# p4_power_measure_ch1.net
KiCad netlist of a schematic drawn in Altium Designer
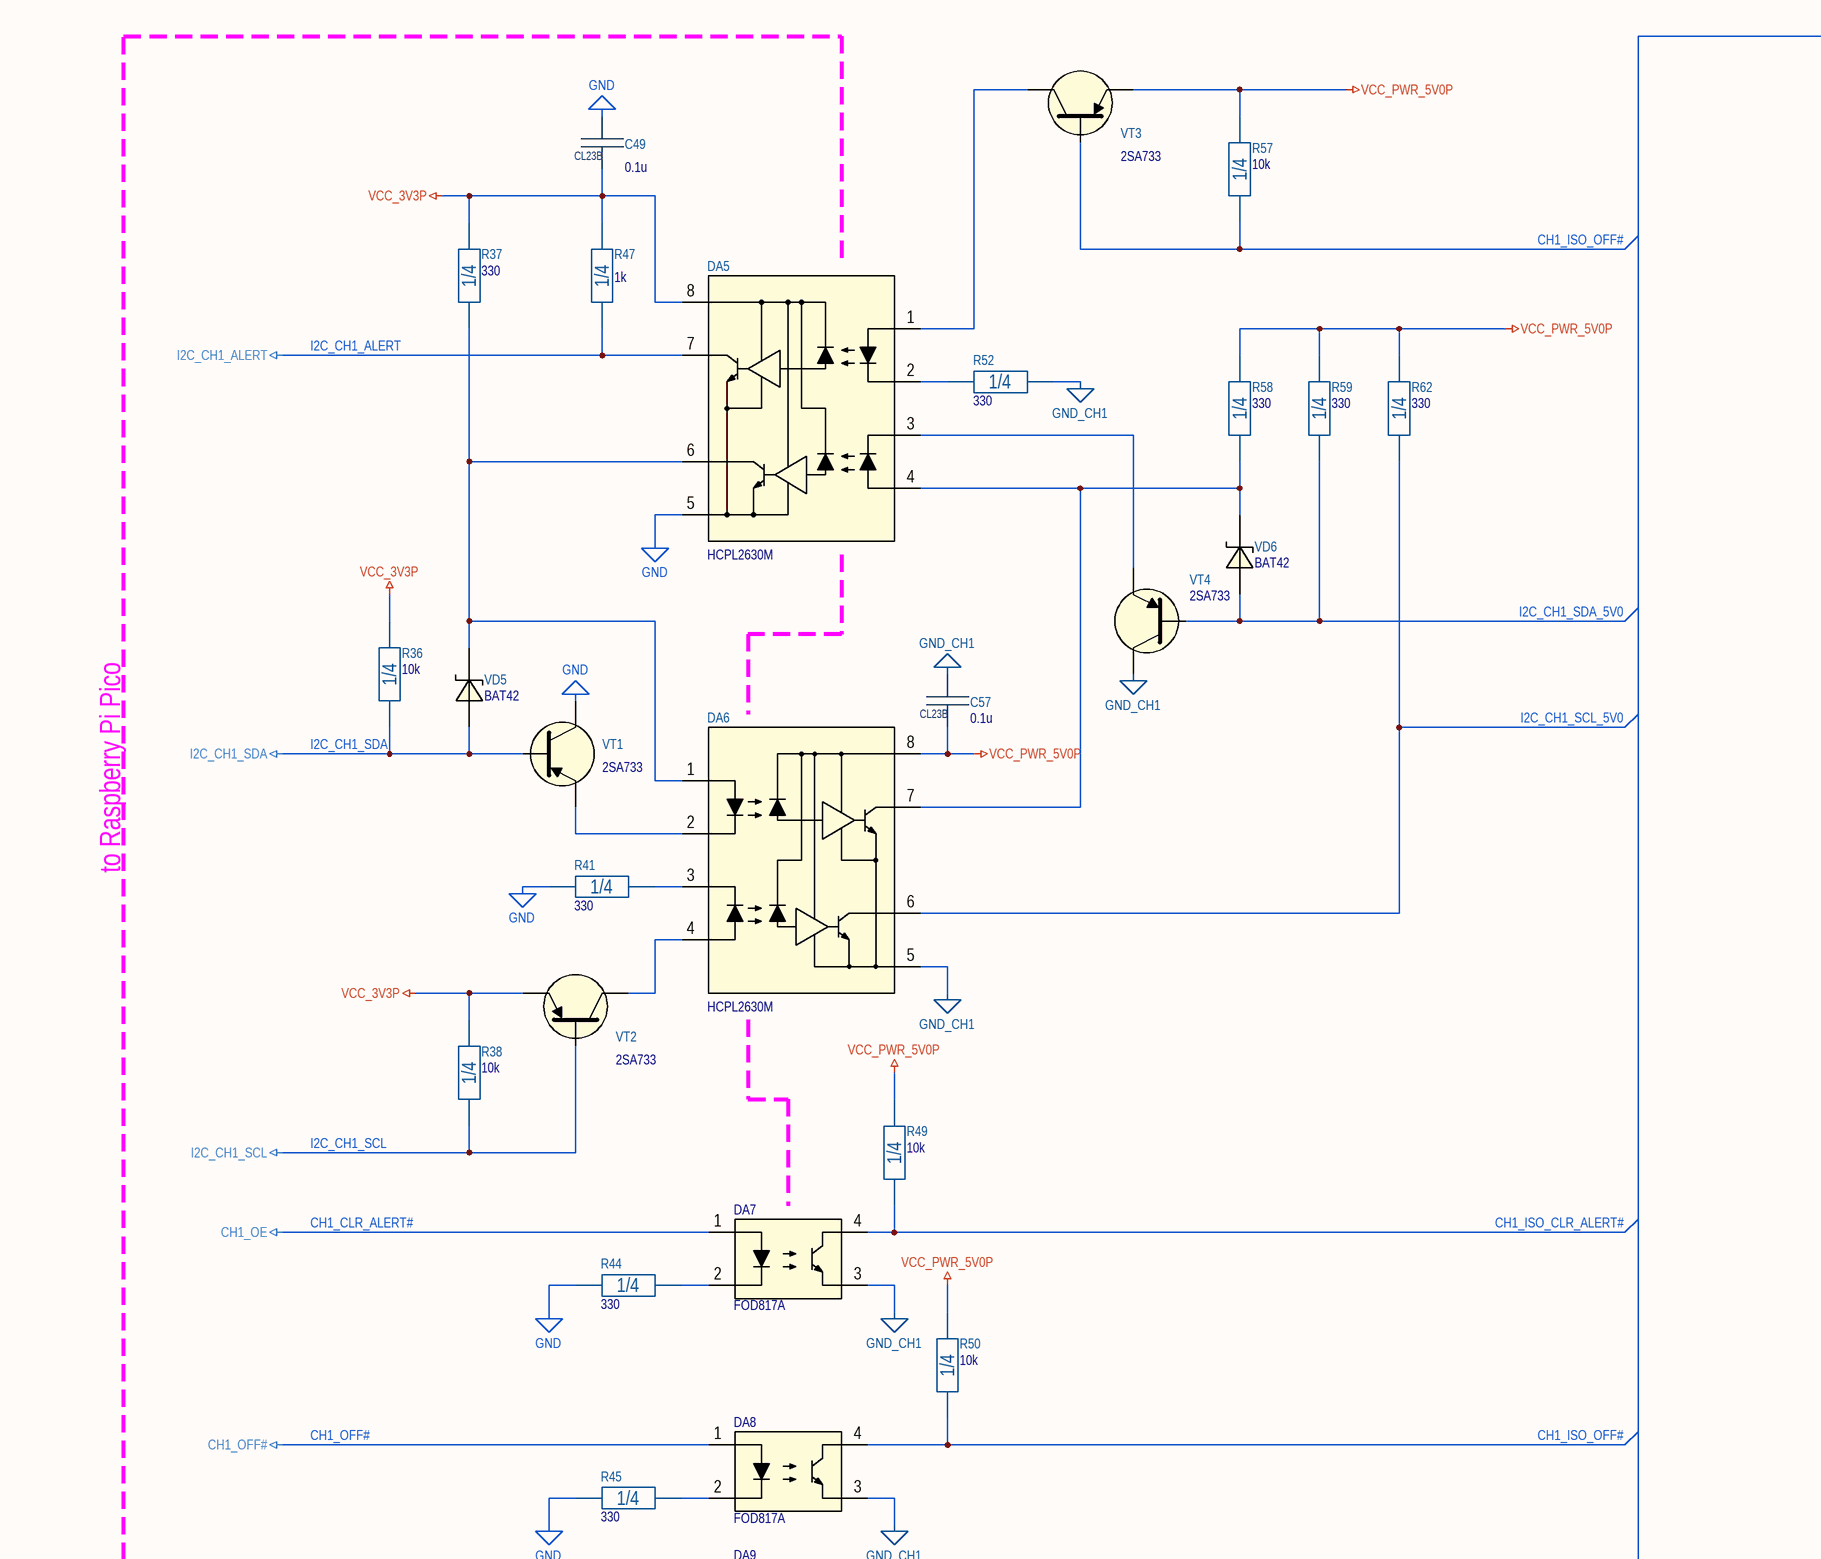
[diagram p0: p4_power_measure_ch1.SchDoc, top left]
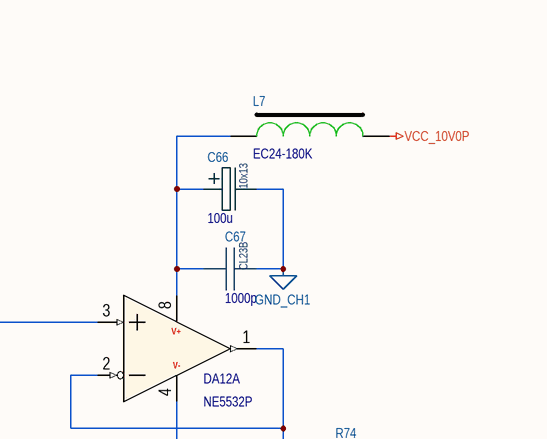
[diagram p1: p4_power_measure_ch1.SchDoc, top right]
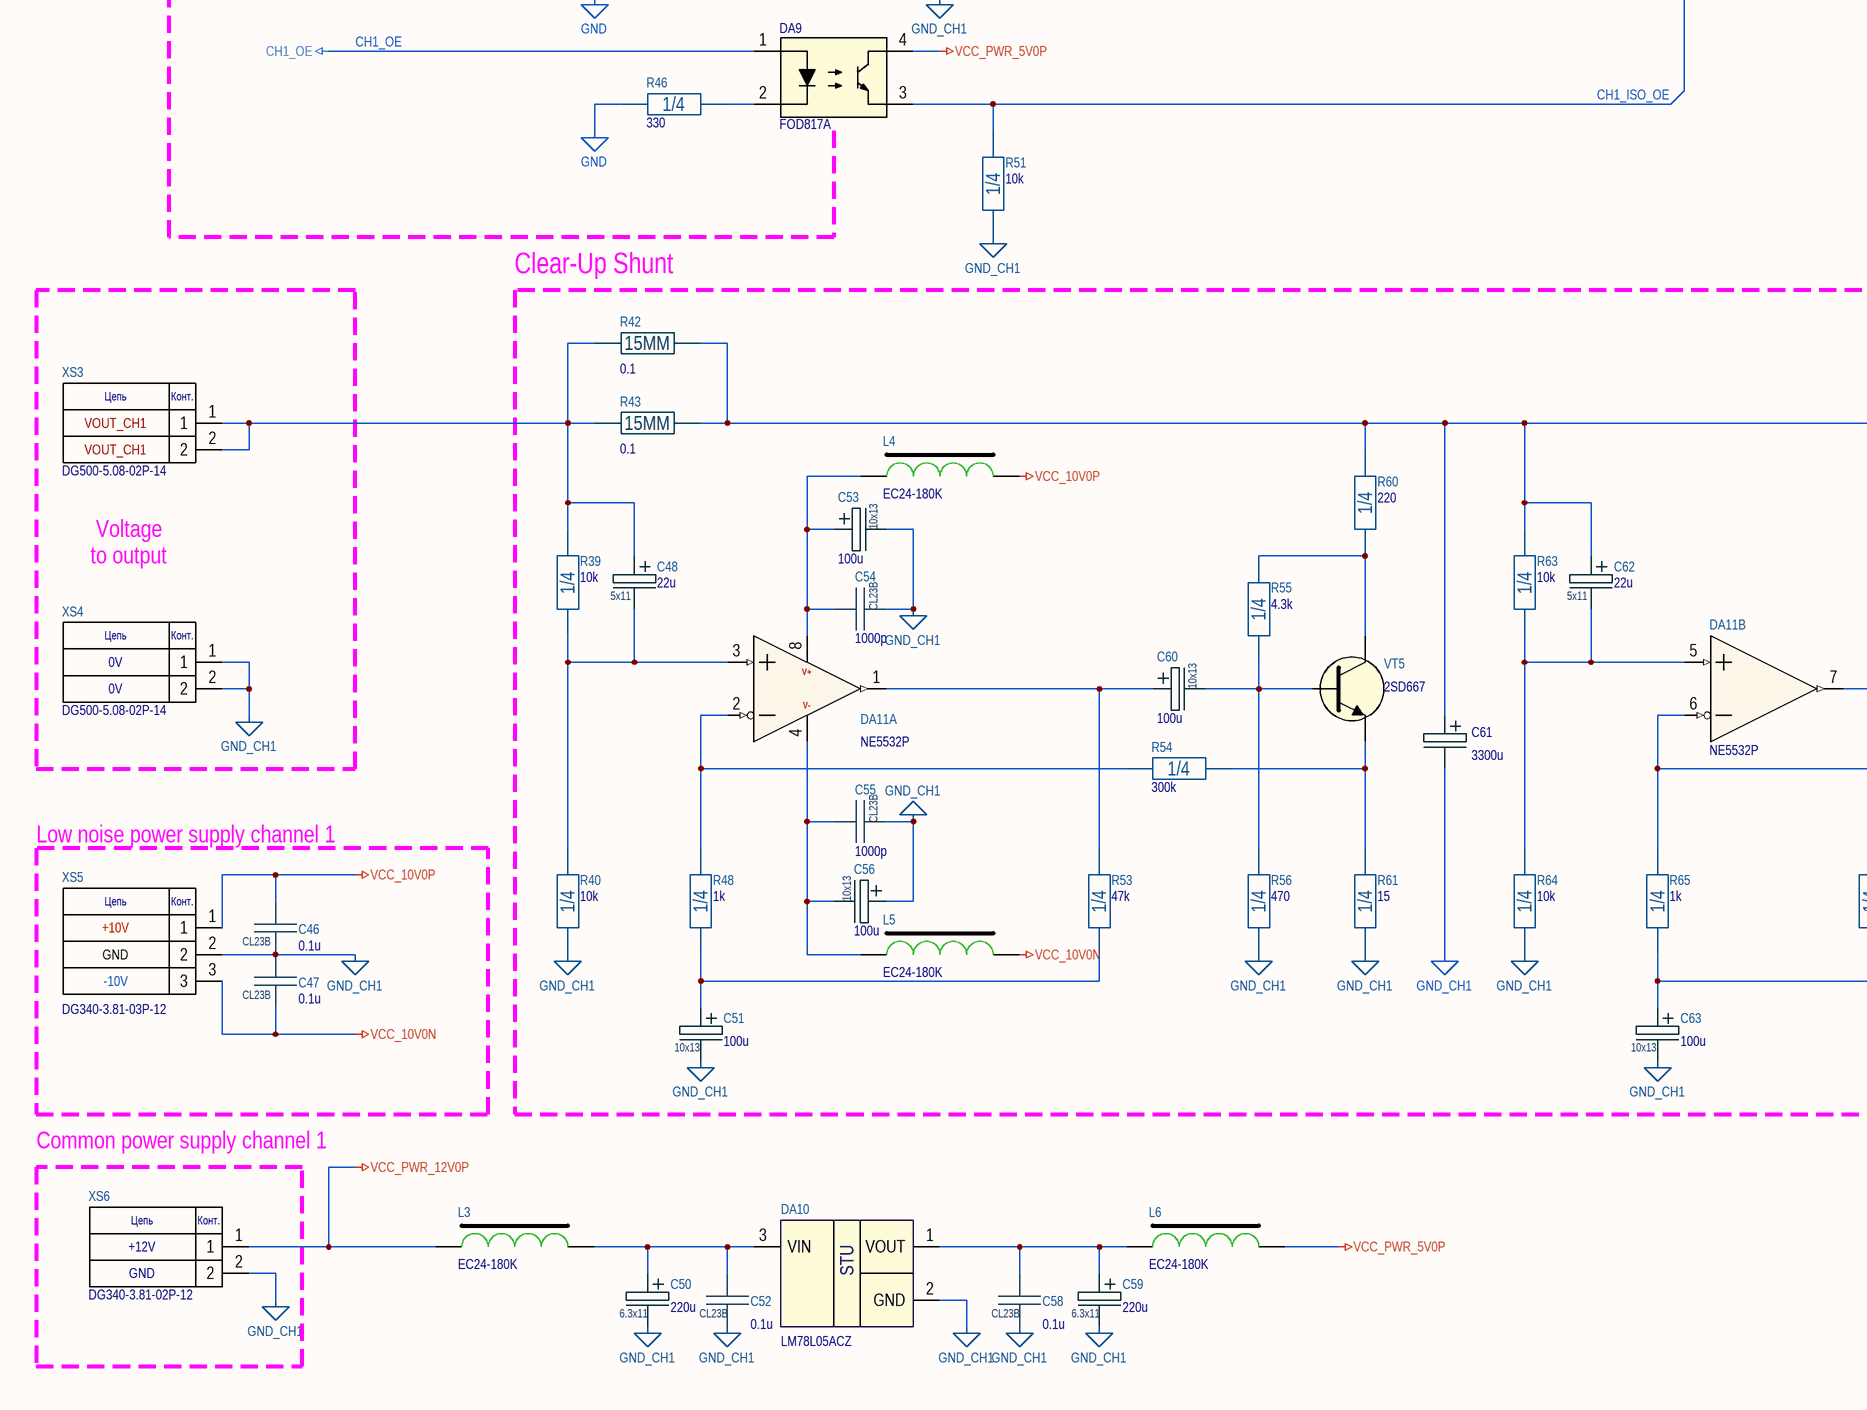
[diagram p2: p4_power_measure_ch1.SchDoc, bottom left]
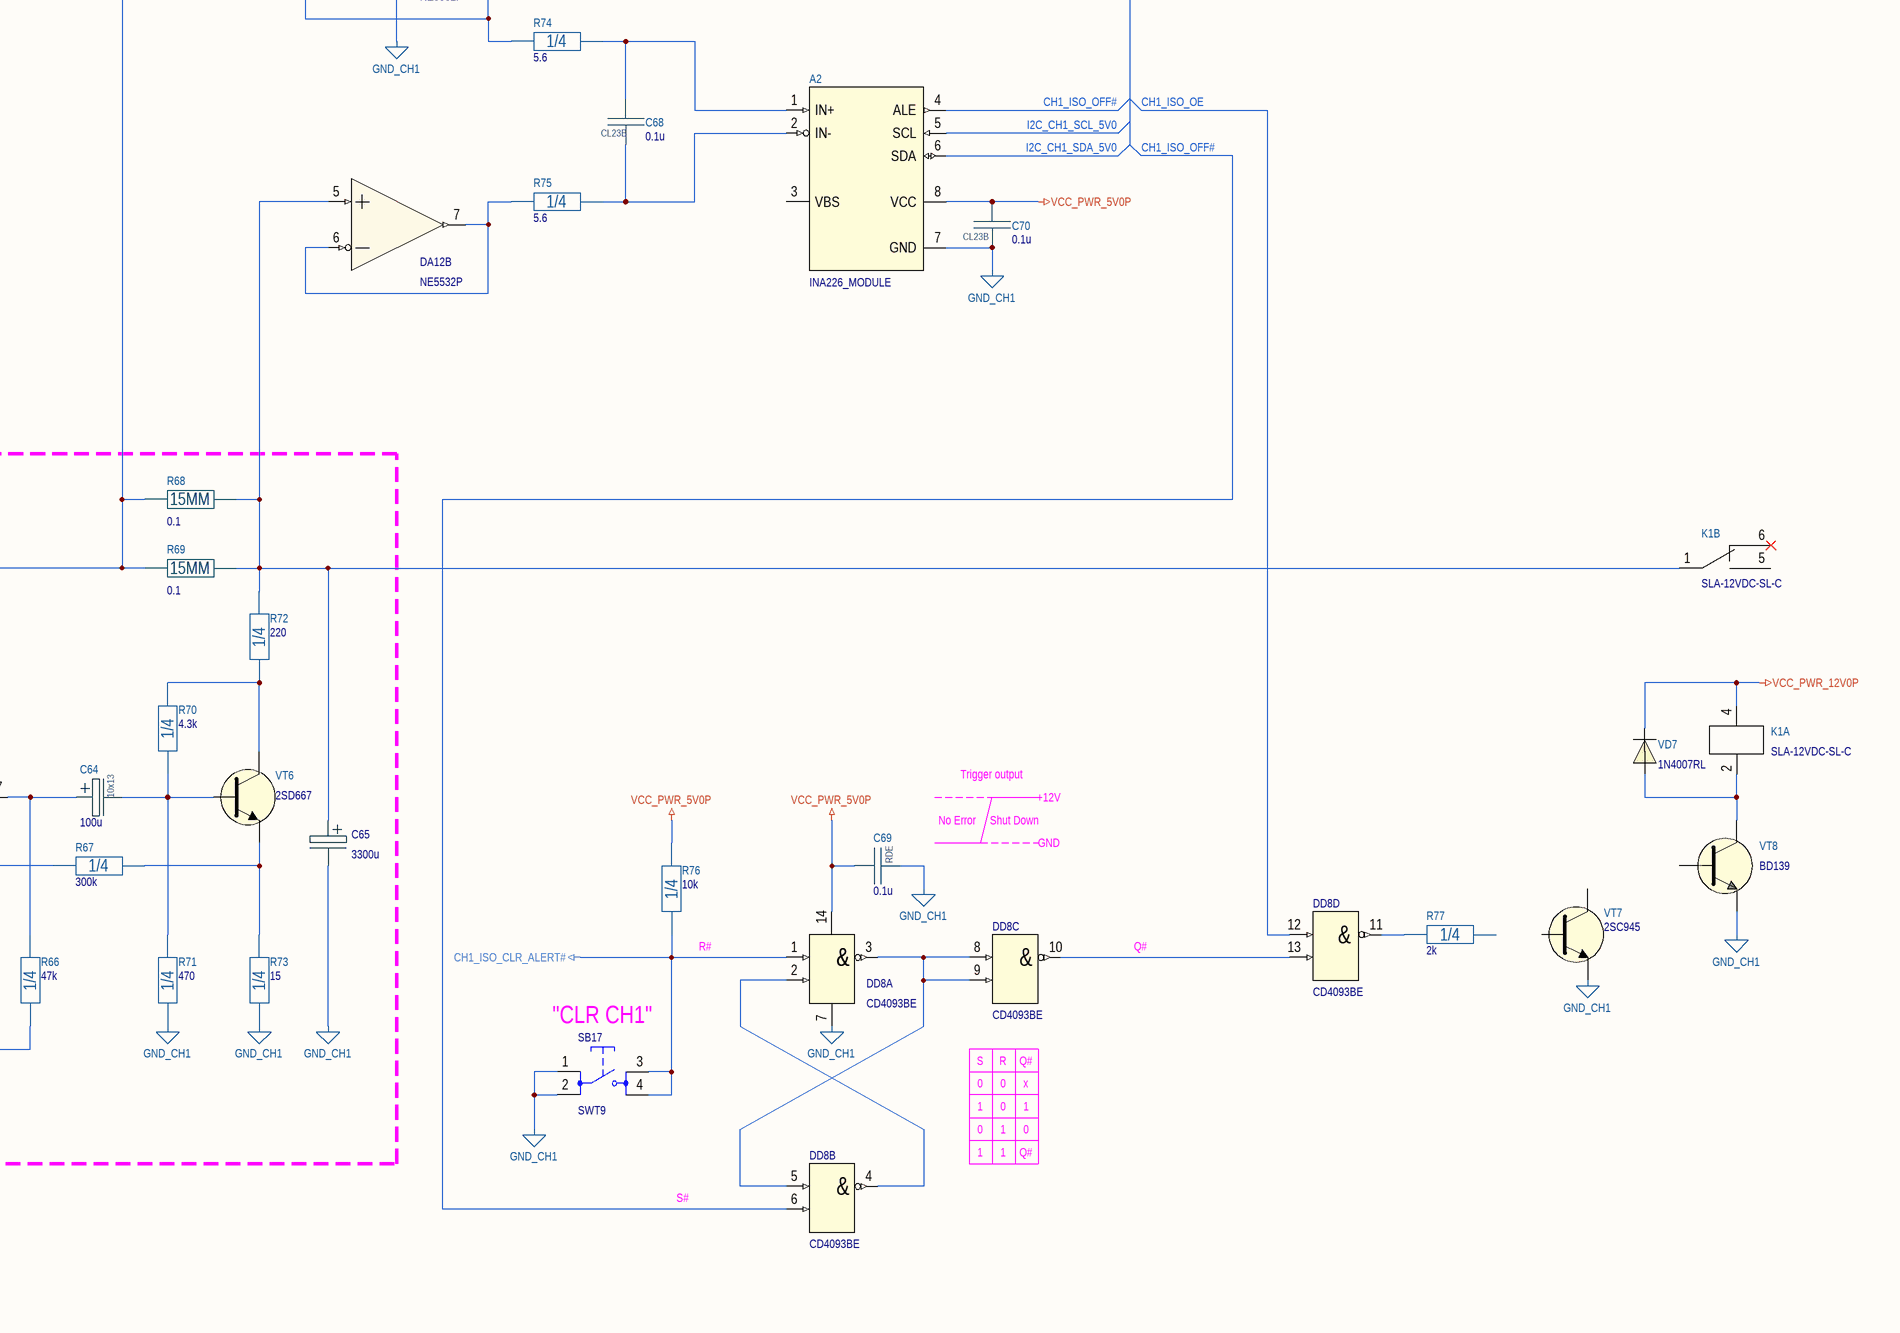
[diagram p3: p4_power_measure_ch1.SchDoc, bottom right]

(export (version "E")
  (design (tool "Eeschema 10.0.6"))
  (components
    (comp (ref "A2")
      (value "INA226_MODULE")
      (footprint "PcbLib_Others:INA226_MODULE_VERT")
      (description "20x20mm module with INA226")
      (libsource (lib "Schlib_OtherComponents") (part "INA226_MODULE"))
    )
    (comp (ref "C46")
      (value "0.1u")
      (footprint "PcbLib_RC:CL23B_7.2x2.5")
      (description "Box-type metallized polyester film capacitor")
      (fields
        (field (name "TOLERANCE") "± * %")
        (field (name "VOLTAGE") "63V")
        (field (name "PACKAGE") "CL23B")
      )
      (libsource (lib "Schlib_RC") (part "CL23B"))
    )
    (comp (ref "C47")
      (value "0.1u")
      (footprint "PcbLib_RC:CL23B_7.2x2.5")
      (description "Box-type metallized polyester film capacitor")
      (fields
        (field (name "TOLERANCE") "± * %")
        (field (name "VOLTAGE") "63V")
        (field (name "PACKAGE") "CL23B")
      )
      (libsource (lib "Schlib_RC") (part "CL23B"))
    )
    (comp (ref "C48")
      (value "22u")
      (footprint "PcbLib_RC:ECAP5X11X2.0_BRW")
      (description "Aluminium capacitor")
      (fields
        (field (name "TOLERANCE") "± 20 %")
        (field (name "VOLTAGE") "63V")
        (field (name "PACKAGE") "5x11")
      )
      (libsource (lib "Schlib_RC") (part "C_ECAP"))
    )
    (comp (ref "C49")
      (value "0.1u")
      (footprint "PcbLib_RC:CL23B_7.2x2.5")
      (description "Box-type metallized polyester film capacitor")
      (fields
        (field (name "TOLERANCE") "± * %")
        (field (name "VOLTAGE") "63V")
        (field (name "PACKAGE") "CL23B")
      )
      (libsource (lib "Schlib_RC") (part "CL23B"))
    )
    (comp (ref "C50")
      (value "220u")
      (footprint "PcbLib_RC:ECAP6.3X11X2.5_BRW")
      (description "Aluminium capacitor")
      (fields
        (field (name "TOLERANCE") "± 20 %")
        (field (name "VOLTAGE") "16V")
        (field (name "PACKAGE") "6.3x11")
      )
      (libsource (lib "Schlib_RC") (part "C_ECAP"))
    )
    (comp (ref "C51")
      (value "100u")
      (footprint "PcbLib_RC:ECAP10X13X5_BRW")
      (description "Aluminium capacitor")
      (fields
        (field (name "TOLERANCE") "± 20 %")
        (field (name "VOLTAGE") "63V")
        (field (name "PACKAGE") "10x13")
      )
      (libsource (lib "Schlib_RC") (part "C_ECAP"))
    )
    (comp (ref "C52")
      (value "0.1u")
      (footprint "PcbLib_RC:CL23B_7.2x2.5")
      (description "Box-type metallized polyester film capacitor")
      (fields
        (field (name "TOLERANCE") "± * %")
        (field (name "VOLTAGE") "63V")
        (field (name "PACKAGE") "CL23B")
      )
      (libsource (lib "Schlib_RC") (part "CL23B"))
    )
    (comp (ref "C53")
      (value "100u")
      (footprint "PcbLib_RC:ECAP10X13X5_BRW")
      (description "Aluminium capacitor")
      (fields
        (field (name "TOLERANCE") "± 20 %")
        (field (name "VOLTAGE") "63V")
        (field (name "PACKAGE") "10x13")
      )
      (libsource (lib "Schlib_RC") (part "C_ECAP"))
    )
    (comp (ref "C54")
      (value "1000p")
      (footprint "PcbLib_RC:CL23B_7.2x2.5")
      (description "Box-type metallized polyester film capacitor")
      (fields
        (field (name "TOLERANCE") "± * %")
        (field (name "VOLTAGE") "63V")
        (field (name "PACKAGE") "CL23B")
      )
      (libsource (lib "Schlib_RC") (part "CL23B"))
    )
    (comp (ref "C55")
      (value "1000p")
      (footprint "PcbLib_RC:CL23B_7.2x2.5")
      (description "Box-type metallized polyester film capacitor")
      (fields
        (field (name "TOLERANCE") "± * %")
        (field (name "VOLTAGE") "63V")
        (field (name "PACKAGE") "CL23B")
      )
      (libsource (lib "Schlib_RC") (part "CL23B"))
    )
    (comp (ref "C56")
      (value "100u")
      (footprint "PcbLib_RC:ECAP10X13X5_BRW")
      (description "Aluminium capacitor")
      (fields
        (field (name "TOLERANCE") "± 20 %")
        (field (name "VOLTAGE") "63V")
        (field (name "PACKAGE") "10x13")
      )
      (libsource (lib "Schlib_RC") (part "C_ECAP"))
    )
    (comp (ref "C57")
      (value "0.1u")
      (footprint "PcbLib_RC:CL23B_7.2x2.5")
      (description "Box-type metallized polyester film capacitor")
      (fields
        (field (name "TOLERANCE") "± * %")
        (field (name "VOLTAGE") "63V")
        (field (name "PACKAGE") "CL23B")
      )
      (libsource (lib "Schlib_RC") (part "CL23B"))
    )
    (comp (ref "C58")
      (value "0.1u")
      (footprint "PcbLib_RC:CL23B_7.2x2.5")
      (description "Box-type metallized polyester film capacitor")
      (fields
        (field (name "TOLERANCE") "± * %")
        (field (name "VOLTAGE") "63V")
        (field (name "PACKAGE") "CL23B")
      )
      (libsource (lib "Schlib_RC") (part "CL23B"))
    )
    (comp (ref "C59")
      (value "220u")
      (footprint "PcbLib_RC:ECAP6.3X11X2.5_BRW")
      (description "Aluminium capacitor")
      (fields
        (field (name "TOLERANCE") "± 20 %")
        (field (name "VOLTAGE") "16V")
        (field (name "PACKAGE") "6.3x11")
      )
      (libsource (lib "Schlib_RC") (part "C_ECAP"))
    )
    (comp (ref "C60")
      (value "100u")
      (footprint "PcbLib_RC:ECAP10X13X5_BRW")
      (description "Aluminium capacitor")
      (fields
        (field (name "TOLERANCE") "± 20 %")
        (field (name "VOLTAGE") "63V")
        (field (name "PACKAGE") "10x13")
      )
      (libsource (lib "Schlib_RC") (part "C_ECAP"))
    )
    (comp (ref "C61")
      (value "3300u")
      (footprint "PcbLib_RC:ECAP16X36X75_BLK")
      (description "Aluminium capacitor")
      (fields (field (name "TOLERANCE") "± 20 %") (field (name "VOLTAGE") "50V"))
      (libsource (lib "Schlib_RC") (part "C_ECAP"))
    )
    (comp (ref "C62")
      (value "22u")
      (footprint "PcbLib_RC:ECAP5X11X2.0_BRW")
      (description "Aluminium capacitor")
      (fields
        (field (name "TOLERANCE") "± 20 %")
        (field (name "VOLTAGE") "63V")
        (field (name "PACKAGE") "5x11")
      )
      (libsource (lib "Schlib_RC") (part "C_ECAP"))
    )
    (comp (ref "C63")
      (value "100u")
      (footprint "PcbLib_RC:ECAP10X13X5_BRW")
      (description "Aluminium capacitor")
      (fields
        (field (name "TOLERANCE") "± 20 %")
        (field (name "VOLTAGE") "63V")
        (field (name "PACKAGE") "10x13")
      )
      (libsource (lib "Schlib_RC") (part "C_ECAP"))
    )
    (comp (ref "C64")
      (value "100u")
      (footprint "PcbLib_RC:ECAP10X13X5_BRW")
      (description "Aluminium capacitor")
      (fields
        (field (name "TOLERANCE") "± 20 %")
        (field (name "VOLTAGE") "63V")
        (field (name "PACKAGE") "10x13")
      )
      (libsource (lib "Schlib_RC") (part "C_ECAP"))
    )
    (comp (ref "C65")
      (value "3300u")
      (footprint "PcbLib_RC:ECAP16X36X75_BLK")
      (description "Aluminium capacitor")
      (fields (field (name "TOLERANCE") "± 20 %") (field (name "VOLTAGE") "50V"))
      (libsource (lib "Schlib_RC") (part "C_ECAP"))
    )
    (comp (ref "C66")
      (value "100u")
      (footprint "PcbLib_RC:ECAP10X13X5_BRW")
      (description "Aluminium capacitor")
      (fields
        (field (name "TOLERANCE") "± 20 %")
        (field (name "VOLTAGE") "63V")
        (field (name "PACKAGE") "10x13")
      )
      (libsource (lib "Schlib_RC") (part "C_ECAP"))
    )
    (comp (ref "C67")
      (value "1000p")
      (footprint "PcbLib_RC:CL23B_7.2x2.5")
      (description "Box-type metallized polyester film capacitor")
      (fields
        (field (name "TOLERANCE") "± * %")
        (field (name "VOLTAGE") "63V")
        (field (name "PACKAGE") "CL23B")
      )
      (libsource (lib "Schlib_RC") (part "CL23B"))
    )
    (comp (ref "C68")
      (value "0.1u")
      (footprint "PcbLib_RC:CL23B_7.2x2.5")
      (description "Box-type metallized polyester film capacitor")
      (fields
        (field (name "TOLERANCE") "± * %")
        (field (name "VOLTAGE") "63V")
        (field (name "PACKAGE") "CL23B")
      )
      (libsource (lib "Schlib_RC") (part "CL23B"))
    )
    (comp (ref "C69")
      (value "0.1u")
      (footprint "PcbLib_RC:RDE_1P1")
      (description "MLCC radial lead type with epoxy coat (RDE Series)")
      (fields
        (field (name "TOLERANCE") "± 10 %")
        (field (name "VOLTAGE") "100V")
        (field (name "PACKAGE") "RDE")
      )
      (libsource (lib "Schlib_RC") (part "RDE_CAP"))
    )
    (comp (ref "C70")
      (value "0.1u")
      (footprint "PcbLib_RC:CL23B_7.2x2.5")
      (description "Box-type metallized polyester film capacitor")
      (fields
        (field (name "TOLERANCE") "± * %")
        (field (name "VOLTAGE") "63V")
        (field (name "PACKAGE") "CL23B")
      )
      (libsource (lib "Schlib_RC") (part "CL23B"))
    )
    (comp (ref "DA5")
      (value "HCPL2630M")
      (footprint "PcbLib_ICs:DIP-8P-M01")
      (description "Dual-Channel High-Speed 10 MBit/s Logic Gate Optocouplers")
      (fields (field (name "MANUFACTURER") "ON Semiconductor"))
      (libsource (lib "Schlib_ONSemiconductor") (part "HCPL2630M"))
    )
    (comp (ref "DA6")
      (value "HCPL2630M")
      (footprint "PcbLib_ICs:DIP-8P-M01")
      (description "Dual-Channel High-Speed 10 MBit/s Logic Gate Optocouplers")
      (fields (field (name "MANUFACTURER") "ON Semiconductor"))
      (libsource (lib "Schlib_ONSemiconductor") (part "HCPL2630M"))
    )
    (comp (ref "DA7")
      (value "FOD817A")
      (footprint "PcbLib_ICs:DIP-4P")
      (description "5kV Phototransistor Optocoupler")
      (fields (field (name "MANUFACTURER") "ON Semiconductor"))
      (libsource (lib "Schlib_ONSemiconductor") (part "FOD817A"))
    )
    (comp (ref "DA8")
      (value "FOD817A")
      (footprint "PcbLib_ICs:DIP-4P")
      (description "5kV Phototransistor Optocoupler")
      (fields (field (name "MANUFACTURER") "ON Semiconductor"))
      (libsource (lib "Schlib_ONSemiconductor") (part "FOD817A"))
    )
    (comp (ref "DA9")
      (value "FOD817A")
      (footprint "PcbLib_ICs:DIP-4P")
      (description "5kV Phototransistor Optocoupler")
      (fields (field (name "MANUFACTURER") "ON Semiconductor"))
      (libsource (lib "Schlib_ONSemiconductor") (part "FOD817A"))
    )
    (comp (ref "DA10")
      (value "LM78L05ACZ")
      (footprint "PcbLib_ICs:TO-92 (VERTICAL,LINE)")
      (description "100-mA Fixed Output Linear Regulator")
      (fields (field (name "MANUFACTURER") "Texas Instruments"))
      (libsource (lib "Schlib_Texas_Instruments") (part "LM78L05ACZ"))
    )
    (comp (ref "DA11")
      (value "NE5532P")
      (footprint "PcbLib_ICs:DIP-8P-M01")
      (description "DUAL LOW-NOISE OPERATIONAL AMPLIFIERS")
      (fields (field (name "MANUFACTURER") "Texas Instruments"))
      (libsource (lib "Schlib_Texas_Instruments") (part "NE5532P"))
    )
    (comp (ref "DA12")
      (value "NE5532P")
      (footprint "PcbLib_ICs:DIP-8P-M01")
      (description "DUAL LOW-NOISE OPERATIONAL AMPLIFIERS")
      (fields (field (name "MANUFACTURER") "Texas Instruments"))
      (libsource (lib "Schlib_Texas_Instruments") (part "NE5532P"))
    )
    (comp (ref "DD8")
      (value "CD4093BE")
      (footprint "PcbLib_ICs:DIP-14P-M02")
      (description "Quad 2-Input NAND Gate Schmitt Triggers")
      (fields (field (name "MANUFACTURER") "Texas Instruments"))
      (libsource (lib "Schlib_Texas_Instruments") (part "CD4093BE"))
    )
    (comp (ref "K1")
      (value "SLA-12VDC-SL-C")
      (footprint "PcbLib_Others:RELAY_32x27.5MM")
      (description "Subminature high power relay 4P 30A")
      (fields (field (name "MANUFACTURER") "Songle Relay"))
      (libsource (lib "") (part "SLA-12VDC-SL-C_1"))
    )
    (comp (ref "L3")
      (value "EC24-180K")
      (footprint "PcbLib_RC:EC24_GREEN")
      (description "Axial leaded coated inductors")
      (fields (field (name "MANUFACTURER") "3L Electronic"))
      (libsource (lib "Schlib_RC") (part "EC24"))
    )
    (comp (ref "L4")
      (value "EC24-180K")
      (footprint "PcbLib_RC:EC24_GREEN")
      (description "Axial leaded coated inductors")
      (fields (field (name "MANUFACTURER") "3L Electronic"))
      (libsource (lib "Schlib_RC") (part "EC24"))
    )
    (comp (ref "L5")
      (value "EC24-180K")
      (footprint "PcbLib_RC:EC24_GREEN")
      (description "Axial leaded coated inductors")
      (fields (field (name "MANUFACTURER") "3L Electronic"))
      (libsource (lib "Schlib_RC") (part "EC24"))
    )
    (comp (ref "L6")
      (value "EC24-180K")
      (footprint "PcbLib_RC:EC24_GREEN")
      (description "Axial leaded coated inductors")
      (fields (field (name "MANUFACTURER") "3L Electronic"))
      (libsource (lib "Schlib_RC") (part "EC24"))
    )
    (comp (ref "L7")
      (value "EC24-180K")
      (footprint "PcbLib_RC:EC24_GREEN")
      (description "Axial leaded coated inductors")
      (fields (field (name "MANUFACTURER") "3L Electronic"))
      (libsource (lib "Schlib_RC") (part "EC24"))
    )
    (comp (ref "R36")
      (value "10k")
      (footprint "PcbLib_RC:CFR-25")
      (description "Resistor 1/4W")
      (fields
        (field (name "TOLERANCE") "± 1 %")
        (field (name "PART NUMBER") "MFR-25FTF52-10K")
        (field (name "PACKAGE") "1/4")
      )
      (libsource (lib "Schlib_RC") (part "CF25"))
    )
    (comp (ref "R37")
      (value "330")
      (footprint "PcbLib_RC:CFR-25")
      (description "Resistor 1/4W")
      (fields
        (field (name "TOLERANCE") "± 1 %")
        (field (name "PART NUMBER") "MFR-25FTF52-330R")
        (field (name "PACKAGE") "1/4")
      )
      (libsource (lib "Schlib_RC") (part "CF25"))
    )
    (comp (ref "R38")
      (value "10k")
      (footprint "PcbLib_RC:CFR-25")
      (description "Resistor 1/4W")
      (fields
        (field (name "TOLERANCE") "± 1 %")
        (field (name "PART NUMBER") "MFR-25FTF52-10K")
        (field (name "PACKAGE") "1/4")
      )
      (libsource (lib "Schlib_RC") (part "CF25"))
    )
    (comp (ref "R39")
      (value "10k")
      (footprint "PcbLib_RC:CFR-25")
      (description "Resistor 1/4W")
      (fields
        (field (name "TOLERANCE") "± 1 %")
        (field (name "PART NUMBER") "MFR-25FTF52-10K")
        (field (name "PACKAGE") "1/4")
      )
      (libsource (lib "Schlib_RC") (part "CF25"))
    )
    (comp (ref "R40")
      (value "10k")
      (footprint "PcbLib_RC:CFR-25")
      (description "Resistor 1/4W")
      (fields
        (field (name "TOLERANCE") "± 1 %")
        (field (name "PART NUMBER") "MFR-25FTF52-10K")
        (field (name "PACKAGE") "1/4")
      )
      (libsource (lib "Schlib_RC") (part "CF25"))
    )
    (comp (ref "R41")
      (value "330")
      (footprint "PcbLib_RC:CFR-25")
      (description "Resistor 1/4W")
      (fields
        (field (name "TOLERANCE") "± 1 %")
        (field (name "PART NUMBER") "MFR-25FTF52-330R")
        (field (name "PACKAGE") "1/4")
      )
      (libsource (lib "Schlib_RC") (part "CF25"))
    )
    (comp (ref "R42")
      (value "0.1")
      (footprint "PcbLib_RC:CURRENT_SENSE_15x18mm")
      (description "Constantan shunt resistor, pitch = 15mm")
      (fields (field (name "TOLERANCE") "±  %") (field (name "PACKAGE") "15MM"))
      (libsource (lib "Schlib_RC") (part "SHUNT_15MM"))
    )
    (comp (ref "R43")
      (value "0.1")
      (footprint "PcbLib_RC:CURRENT_SENSE_15x18mm")
      (description "Constantan shunt resistor, pitch = 15mm")
      (fields (field (name "TOLERANCE") "±  %") (field (name "PACKAGE") "15MM"))
      (libsource (lib "Schlib_RC") (part "SHUNT_15MM"))
    )
    (comp (ref "R44")
      (value "330")
      (footprint "PcbLib_RC:CFR-25")
      (description "Resistor 1/4W")
      (fields
        (field (name "TOLERANCE") "± 1 %")
        (field (name "PART NUMBER") "MFR-25FTF52-330R")
        (field (name "PACKAGE") "1/4")
      )
      (libsource (lib "Schlib_RC") (part "CF25"))
    )
    (comp (ref "R45")
      (value "330")
      (footprint "PcbLib_RC:CFR-25")
      (description "Resistor 1/4W")
      (fields
        (field (name "TOLERANCE") "± 1 %")
        (field (name "PART NUMBER") "MFR-25FTF52-330R")
        (field (name "PACKAGE") "1/4")
      )
      (libsource (lib "Schlib_RC") (part "CF25"))
    )
    (comp (ref "R46")
      (value "330")
      (footprint "PcbLib_RC:CFR-25")
      (description "Resistor 1/4W")
      (fields
        (field (name "TOLERANCE") "± 1 %")
        (field (name "PART NUMBER") "MFR-25FTF52-330R")
        (field (name "PACKAGE") "1/4")
      )
      (libsource (lib "Schlib_RC") (part "CF25"))
    )
    (comp (ref "R47")
      (value "1k")
      (footprint "PcbLib_RC:CFR-25")
      (description "Resistor 1/4W")
      (fields
        (field (name "TOLERANCE") "± 1 %")
        (field (name "PART NUMBER") "MFR-25FTF52-1K")
        (field (name "PACKAGE") "1/4")
      )
      (libsource (lib "Schlib_RC") (part "CF25"))
    )
    (comp (ref "R48")
      (value "1k")
      (footprint "PcbLib_RC:CFR-25")
      (description "Resistor 1/4W")
      (fields
        (field (name "TOLERANCE") "± 1 %")
        (field (name "PART NUMBER") "MFR-25FTF52-1K")
        (field (name "PACKAGE") "1/4")
      )
      (libsource (lib "Schlib_RC") (part "CF25"))
    )
    (comp (ref "R49")
      (value "10k")
      (footprint "PcbLib_RC:CFR-25")
      (description "Resistor 1/4W")
      (fields
        (field (name "TOLERANCE") "± 1 %")
        (field (name "PART NUMBER") "MFR-25FTF52-10K")
        (field (name "PACKAGE") "1/4")
      )
      (libsource (lib "Schlib_RC") (part "CF25"))
    )
    (comp (ref "R50")
      (value "10k")
      (footprint "PcbLib_RC:CFR-25")
      (description "Resistor 1/4W")
      (fields
        (field (name "TOLERANCE") "± 1 %")
        (field (name "PART NUMBER") "MFR-25FTF52-10K")
        (field (name "PACKAGE") "1/4")
      )
      (libsource (lib "Schlib_RC") (part "CF25"))
    )
    (comp (ref "R51")
      (value "10k")
      (footprint "PcbLib_RC:CFR-25")
      (description "Resistor 1/4W")
      (fields
        (field (name "TOLERANCE") "± 1 %")
        (field (name "PART NUMBER") "MFR-25FTF52-10K")
        (field (name "PACKAGE") "1/4")
      )
      (libsource (lib "Schlib_RC") (part "CF25"))
    )
    (comp (ref "R52")
      (value "330")
      (footprint "PcbLib_RC:CFR-25")
      (description "Resistor 1/4W")
      (fields
        (field (name "TOLERANCE") "± 1 %")
        (field (name "PART NUMBER") "MFR-25FTF52-330R")
        (field (name "PACKAGE") "1/4")
      )
      (libsource (lib "Schlib_RC") (part "CF25"))
    )
    (comp (ref "R53")
      (value "47k")
      (footprint "PcbLib_RC:CFR-25")
      (description "Resistor 1/4W")
      (fields
        (field (name "TOLERANCE") "± 1 %")
        (field (name "PART NUMBER") "MFR-25FTF52-47K")
        (field (name "PACKAGE") "1/4")
      )
      (libsource (lib "Schlib_RC") (part "CF25"))
    )
    (comp (ref "R54")
      (value "300k")
      (footprint "PcbLib_RC:CFR-25")
      (description "Resistor 1/4W")
      (fields
        (field (name "TOLERANCE") "± 1 %")
        (field (name "PART NUMBER") "MFR-25FTF52-300K")
        (field (name "PACKAGE") "1/4")
      )
      (libsource (lib "Schlib_RC") (part "CF25"))
    )
    (comp (ref "R55")
      (value "4.3k")
      (footprint "PcbLib_RC:CFR-25")
      (description "Resistor 1/4W")
      (fields
        (field (name "TOLERANCE") "± 1 %")
        (field (name "PART NUMBER") "MFR-25FTF52-4K3")
        (field (name "PACKAGE") "1/4")
      )
      (libsource (lib "Schlib_RC") (part "CF25"))
    )
    (comp (ref "R56")
      (value "470")
      (footprint "PcbLib_RC:CFR-25")
      (description "Resistor 1/4W")
      (fields
        (field (name "TOLERANCE") "± 1 %")
        (field (name "PART NUMBER") "MFR-25FTF52-470R")
        (field (name "PACKAGE") "1/4")
      )
      (libsource (lib "Schlib_RC") (part "CF25"))
    )
    (comp (ref "R57")
      (value "10k")
      (footprint "PcbLib_RC:CFR-25")
      (description "Resistor 1/4W")
      (fields
        (field (name "TOLERANCE") "± 1 %")
        (field (name "PART NUMBER") "MFR-25FTF52-10K")
        (field (name "PACKAGE") "1/4")
      )
      (libsource (lib "Schlib_RC") (part "CF25"))
    )
    (comp (ref "R58")
      (value "330")
      (footprint "PcbLib_RC:CFR-25")
      (description "Resistor 1/4W")
      (fields
        (field (name "TOLERANCE") "± 1 %")
        (field (name "PART NUMBER") "MFR-25FTF52-330R")
        (field (name "PACKAGE") "1/4")
      )
      (libsource (lib "Schlib_RC") (part "CF25"))
    )
    (comp (ref "R59")
      (value "330")
      (footprint "PcbLib_RC:CFR-25")
      (description "Resistor 1/4W")
      (fields
        (field (name "TOLERANCE") "± 1 %")
        (field (name "PART NUMBER") "MFR-25FTF52-330R")
        (field (name "PACKAGE") "1/4")
      )
      (libsource (lib "Schlib_RC") (part "CF25"))
    )
    (comp (ref "R60")
      (value "220")
      (footprint "PcbLib_RC:CFR-25")
      (description "Resistor 1/4W")
      (fields
        (field (name "TOLERANCE") "± 1 %")
        (field (name "PART NUMBER") "MFR-25FTF52-220R")
        (field (name "PACKAGE") "1/4")
      )
      (libsource (lib "Schlib_RC") (part "CF25"))
    )
    (comp (ref "R61")
      (value "15")
      (footprint "PcbLib_RC:CFR-25")
      (description "Resistor 1/4W")
      (fields
        (field (name "TOLERANCE") "± 1 %")
        (field (name "PART NUMBER") "MFR-25FTF52-15R")
        (field (name "PACKAGE") "1/4")
      )
      (libsource (lib "Schlib_RC") (part "CF25"))
    )
    (comp (ref "R62")
      (value "330")
      (footprint "PcbLib_RC:CFR-25")
      (description "Resistor 1/4W")
      (fields
        (field (name "TOLERANCE") "± 1 %")
        (field (name "PART NUMBER") "MFR-25FTF52-330R")
        (field (name "PACKAGE") "1/4")
      )
      (libsource (lib "Schlib_RC") (part "CF25"))
    )
    (comp (ref "R63")
      (value "10k")
      (footprint "PcbLib_RC:CFR-25")
      (description "Resistor 1/4W")
      (fields
        (field (name "TOLERANCE") "± 1 %")
        (field (name "PART NUMBER") "MFR-25FTF52-10K")
        (field (name "PACKAGE") "1/4")
      )
      (libsource (lib "Schlib_RC") (part "CF25"))
    )
    (comp (ref "R64")
      (value "10k")
      (footprint "PcbLib_RC:CFR-25")
      (description "Resistor 1/4W")
      (fields
        (field (name "TOLERANCE") "± 1 %")
        (field (name "PART NUMBER") "MFR-25FTF52-10K")
        (field (name "PACKAGE") "1/4")
      )
      (libsource (lib "Schlib_RC") (part "CF25"))
    )
    (comp (ref "R65")
      (value "1k")
      (footprint "PcbLib_RC:CFR-25")
      (description "Resistor 1/4W")
      (fields
        (field (name "TOLERANCE") "± 1 %")
        (field (name "PART NUMBER") "MFR-25FTF52-1K")
        (field (name "PACKAGE") "1/4")
      )
      (libsource (lib "Schlib_RC") (part "CF25"))
    )
    (comp (ref "R66")
      (value "47k")
      (footprint "PcbLib_RC:CFR-25")
      (description "Resistor 1/4W")
      (fields
        (field (name "TOLERANCE") "± 1 %")
        (field (name "PART NUMBER") "MFR-25FTF52-47K")
        (field (name "PACKAGE") "1/4")
      )
      (libsource (lib "Schlib_RC") (part "CF25"))
    )
    (comp (ref "R67")
      (value "300k")
      (footprint "PcbLib_RC:CFR-25")
      (description "Resistor 1/4W")
      (fields
        (field (name "TOLERANCE") "± 1 %")
        (field (name "PART NUMBER") "MFR-25FTF52-300K")
        (field (name "PACKAGE") "1/4")
      )
      (libsource (lib "Schlib_RC") (part "CF25"))
    )
    (comp (ref "R68")
      (value "0.1")
      (footprint "PcbLib_RC:CURRENT_SENSE_15x18mm")
      (description "Constantan shunt resistor, pitch = 15mm")
      (fields (field (name "TOLERANCE") "±  %") (field (name "PACKAGE") "15MM"))
      (libsource (lib "Schlib_RC") (part "SHUNT_15MM"))
    )
    (comp (ref "R69")
      (value "0.1")
      (footprint "PcbLib_RC:CURRENT_SENSE_15x18mm")
      (description "Constantan shunt resistor, pitch = 15mm")
      (fields (field (name "TOLERANCE") "±  %") (field (name "PACKAGE") "15MM"))
      (libsource (lib "Schlib_RC") (part "SHUNT_15MM"))
    )
    (comp (ref "R70")
      (value "4.3k")
      (footprint "PcbLib_RC:CFR-25")
      (description "Resistor 1/4W")
      (fields
        (field (name "TOLERANCE") "± 1 %")
        (field (name "PART NUMBER") "MFR-25FTF52-4K3")
        (field (name "PACKAGE") "1/4")
      )
      (libsource (lib "Schlib_RC") (part "CF25"))
    )
    (comp (ref "R71")
      (value "470")
      (footprint "PcbLib_RC:CFR-25")
      (description "Resistor 1/4W")
      (fields
        (field (name "TOLERANCE") "± 1 %")
        (field (name "PART NUMBER") "MFR-25FTF52-470R")
        (field (name "PACKAGE") "1/4")
      )
      (libsource (lib "Schlib_RC") (part "CF25"))
    )
    (comp (ref "R72")
      (value "220")
      (footprint "PcbLib_RC:CFR-25")
      (description "Resistor 1/4W")
      (fields
        (field (name "TOLERANCE") "± 1 %")
        (field (name "PART NUMBER") "MFR-25FTF52-220R")
        (field (name "PACKAGE") "1/4")
      )
      (libsource (lib "Schlib_RC") (part "CF25"))
    )
    (comp (ref "R73")
      (value "15")
      (footprint "PcbLib_RC:CFR-25")
      (description "Resistor 1/4W")
      (fields
        (field (name "TOLERANCE") "± 1 %")
        (field (name "PART NUMBER") "MFR-25FTF52-15R")
        (field (name "PACKAGE") "1/4")
      )
      (libsource (lib "Schlib_RC") (part "CF25"))
    )
    (comp (ref "R74")
      (value "5.6")
      (footprint "PcbLib_RC:CFR-25(VERTICAL)")
      (description "Resistor 1/4W")
      (fields
        (field (name "TOLERANCE") "± 1 %")
        (field (name "PART NUMBER") "MFR-25FTF52-5R6")
        (field (name "PACKAGE") "1/4")
      )
      (libsource (lib "Schlib_RC") (part "CF25"))
    )
    (comp (ref "R75")
      (value "5.6")
      (footprint "PcbLib_RC:CFR-25(VERTICAL)")
      (description "Resistor 1/4W")
      (fields
        (field (name "TOLERANCE") "± 1 %")
        (field (name "PART NUMBER") "MFR-25FTF52-5R6")
        (field (name "PACKAGE") "1/4")
      )
      (libsource (lib "Schlib_RC") (part "CF25"))
    )
    (comp (ref "R76")
      (value "10k")
      (footprint "PcbLib_RC:CFR-25")
      (description "Resistor 1/4W")
      (fields
        (field (name "TOLERANCE") "± 1 %")
        (field (name "PART NUMBER") "MFR-25FTF52-10K")
        (field (name "PACKAGE") "1/4")
      )
      (libsource (lib "Schlib_RC") (part "CF25"))
    )
    (comp (ref "R77")
      (value "2k")
      (footprint "PcbLib_RC:CFR-25")
      (description "Resistor 1/4W")
      (fields
        (field (name "TOLERANCE") "± 1 %")
        (field (name "PART NUMBER") "MFR-25FTF52-2K")
        (field (name "PACKAGE") "1/4")
      )
      (libsource (lib "Schlib_RC") (part "CF25"))
    )
    (comp (ref "SB17")
      (value "SWT9")
      (footprint "PcbLib_Others:SWT9")
      (description "Tact Button (with tact cap SWT9S)")
      (libsource (lib "Schlib_OtherComponents") (part "SWT9"))
    )
    (comp (ref "VD5")
      (value "BAT42")
      (footprint "PcbLib_Discrete:DO-35 GLASS BLUE")
      (description "Small signal schottky diode 30V @ 200mA")
      (fields (field (name "MANUFACTURER") "STMicroelectronics"))
      (libsource (lib "Schlib_STMicroelectronics") (part "BAT42"))
    )
    (comp (ref "VD6")
      (value "BAT42")
      (footprint "PcbLib_Discrete:DO-35 GLASS BLUE")
      (description "Small signal schottky diode 30V @ 200mA")
      (fields (field (name "MANUFACTURER") "STMicroelectronics"))
      (libsource (lib "Schlib_STMicroelectronics") (part "BAT42"))
    )
    (comp (ref "VD7")
      (value "1N4007RL")
      (footprint "PcbLib_Discrete:DO-41")
      (description "1A 1000V Standard Recovery Rectifiers Diode")
      (fields (field (name "MANUFACTURER") "ON Semiconductor"))
      (libsource (lib "Schlib_ONSemiconductor") (part "1N4007RL"))
    )
    (comp (ref "VT1")
      (value "2SA733")
      (footprint "PcbLib_ICs:TO-92 (VERTICAL,LINE)")
      (description "General Purpose p-n-p Transistors")
      (fields (field (name "MANUFACTURER") "NEC"))
      (libsource (lib "Schlib_NEC") (part "2SA733"))
    )
    (comp (ref "VT2")
      (value "2SA733")
      (footprint "PcbLib_ICs:TO-92 (VERTICAL,LINE)")
      (description "General Purpose p-n-p Transistors")
      (fields (field (name "MANUFACTURER") "NEC"))
      (libsource (lib "Schlib_NEC") (part "2SA733"))
    )
    (comp (ref "VT3")
      (value "2SA733")
      (footprint "PcbLib_ICs:TO-92 (VERTICAL,LINE)")
      (description "General Purpose p-n-p Transistors")
      (fields (field (name "MANUFACTURER") "NEC"))
      (libsource (lib "Schlib_NEC") (part "2SA733"))
    )
    (comp (ref "VT4")
      (value "2SA733")
      (footprint "PcbLib_ICs:TO-92 (VERTICAL,LINE)")
      (description "General Purpose p-n-p Transistors")
      (fields (field (name "MANUFACTURER") "NEC"))
      (libsource (lib "Schlib_NEC") (part "2SA733"))
    )
    (comp (ref "VT5")
      (value "2SD667")
      (footprint "PcbLib_ICs:TO-92L (VERTICAL,LINE)")
      (description "General Purpose n-p-n Transistors 120V, 1A")
      (fields (field (name "MANUFACTURER") "Secos"))
      (libsource (lib "Schlib_OtherComponents") (part "2SD667"))
    )
    (comp (ref "VT6")
      (value "2SD667")
      (footprint "PcbLib_ICs:TO-92L (VERTICAL,LINE)")
      (description "General Purpose n-p-n Transistors 120V, 1A")
      (fields (field (name "MANUFACTURER") "Secos"))
      (libsource (lib "Schlib_OtherComponents") (part "2SD667"))
    )
    (comp (ref "VT7")
      (value "2SC945")
      (footprint "PcbLib_ICs:TO-92 (VERTICAL,LINE)")
      (description "General Purpose n-p-n Transistors")
      (fields (field (name "MANUFACTURER") "NEC"))
      (libsource (lib "Schlib_NEC") (part "2SC945"))
    )
    (comp (ref "VT8")
      (value "BD139")
      (footprint "PcbLib_ICs:TO-126 (VERTICAL)")
      (description "General Purpose n-p-n Transistors")
      (fields (field (name "MANUFACTURER") "STMicroelectronics"))
      (libsource (lib "Schlib_STMicroelectronics") (part "BD139"))
    )
    (comp (ref "XS3")
      (value "DG500-5.08-02P-14")
      (footprint "PcbLib_Connectors:DG500-5.08-02P")
      (description "2-way screw terminal, pitch 200mils (5.08mm)")
      (fields (field (name "MANUFACTURER") "DEGSON"))
      (libsource (lib "Schlib_OtherComponents") (part "DG500-5.08-02P-14"))
    )
    (comp (ref "XS4")
      (value "DG500-5.08-02P-14")
      (footprint "PcbLib_Connectors:DG500-5.08-02P")
      (description "2-way screw terminal, pitch 200mils (5.08mm)")
      (fields (field (name "MANUFACTURER") "DEGSON"))
      (libsource (lib "Schlib_OtherComponents") (part "DG500-5.08-02P-14"))
    )
    (comp (ref "XS5")
      (value "DG340-3.81-03P-12")
      (footprint "PcbLib_Connectors:DG340-3.81-03P")
      (description "3-way screw terminal, pitch 150mils (3.81mm)")
      (fields (field (name "MANUFACTURER") "DEGSON"))
      (libsource (lib "Schlib_OtherComponents") (part "DG340-3.81-03P-12"))
    )
    (comp (ref "XS6")
      (value "DG340-3.81-02P-12")
      (footprint "PcbLib_Connectors:DG340-3.81-02P")
      (description "2-way screw terminal, pitch 150mils (3.81mm)")
      (fields (field (name "MANUFACTURER") "DEGSON"))
      (libsource (lib "Schlib_OtherComponents") (part "DG340-3.81-02P-12"))
    )
  )
  (nets
    (net (code "1") (name "/CH1_ISO_OE") (class "Default")
      (node (ref "DA9") (pin "3") (pinfunction "EMITTER_3") (pintype "passive"))
      (node (ref "DD8") (pin "12") (pinfunction "A3_12") (pintype "input"))
      (node (ref "R51") (pin "2") (pinfunction "2_2") (pintype "passive"))
    )
    (net (code "2") (name "/CH1_ISO_OFF#") (class "Default")
      (node (ref "A2") (pin "4") (pinfunction "ALE_4") (pintype "output"))
      (node (ref "DA8") (pin "4") (pinfunction "COLLECTOR_4") (pintype "passive"))
      (node (ref "DD8") (pin "6") (pinfunction "B1_6") (pintype "input"))
      (node (ref "R50") (pin "1") (pinfunction "1_1") (pintype "passive"))
      (node (ref "R57") (pin "1") (pinfunction "1_1") (pintype "passive"))
      (node (ref "VT3") (pin "1") (pinfunction "B_1") (pintype "passive"))
    )
    (net (code "3") (name "/I2C_CH1_SCL_5V0") (class "Default")
      (node (ref "A2") (pin "5") (pinfunction "SCL_5") (pintype "input"))
      (node (ref "DA6") (pin "6") (pinfunction "V02_6") (pintype "passive"))
      (node (ref "R62") (pin "2") (pinfunction "2_2") (pintype "passive"))
    )
    (net (code "4") (name "/I2C_CH1_SDA_5V0") (class "Default")
      (node (ref "A2") (pin "6") (pinfunction "SDA_6") (pintype "bidirectional"))
      (node (ref "R59") (pin "2") (pinfunction "2_2") (pintype "passive"))
      (node (ref "VD6") (pin "2") (pinfunction "ANODE_2") (pintype "passive"))
      (node (ref "VT4") (pin "1") (pinfunction "B_1") (pintype "passive"))
    )
    (net (code "5") (name "CH1_ISO_CLR_ALERT#") (class "Default")
      (node (ref "DA7") (pin "4") (pinfunction "COLLECTOR_4") (pintype "passive"))
      (node (ref "DD8") (pin "1") (pinfunction "A0_1") (pintype "input"))
      (node (ref "R49") (pin "1") (pinfunction "1_1") (pintype "passive"))
      (node (ref "R76") (pin "1") (pinfunction "1_1") (pintype "passive"))
      (node (ref "SB17") (pin "3") (pinfunction "3_3") (pintype "passive"))
      (node (ref "SB17") (pin "4") (pinfunction "4_4") (pintype "passive"))
    )
    (net (code "6") (name "CH1_OE") (class "Default")
      (node (ref "DA7") (pin "1") (pinfunction "ANODE_1") (pintype "passive"))
      (node (ref "DA9") (pin "1") (pinfunction "ANODE_1") (pintype "passive"))
    )
    (net (code "7") (name "CH1_OFF#") (class "Default")
      (node (ref "DA8") (pin "1") (pinfunction "ANODE_1") (pintype "passive"))
    )
    (net (code "8") (name "GND") (class "Default")
      (node (ref "C49") (pin "1") (pinfunction "1_1") (pintype "passive"))
      (node (ref "DA5") (pin "5") (pinfunction "GND_5") (pintype "passive"))
      (node (ref "R41") (pin "1") (pinfunction "1_1") (pintype "passive"))
      (node (ref "R44") (pin "1") (pinfunction "1_1") (pintype "passive"))
      (node (ref "R45") (pin "1") (pinfunction "1_1") (pintype "passive"))
      (node (ref "R46") (pin "1") (pinfunction "1_1") (pintype "passive"))
      (node (ref "VT1") (pin "2") (pinfunction "C_2") (pintype "passive"))
    )
    (net (code "9") (name "GND_CH1") (class "Default")
      (node (ref "A2") (pin "7") (pinfunction "GND_7") (pintype "power_in"))
      (node (ref "C46") (pin "2") (pinfunction "2_2") (pintype "passive"))
      (node (ref "C47") (pin "1") (pinfunction "1_1") (pintype "passive"))
      (node (ref "C50") (pin "2") (pinfunction "2_2") (pintype "passive"))
      (node (ref "C51") (pin "2") (pinfunction "2_2") (pintype "passive"))
      (node (ref "C52") (pin "2") (pinfunction "2_2") (pintype "passive"))
      (node (ref "C53") (pin "2") (pinfunction "2_2") (pintype "passive"))
      (node (ref "C54") (pin "2") (pinfunction "2_2") (pintype "passive"))
      (node (ref "C55") (pin "2") (pinfunction "2_2") (pintype "passive"))
      (node (ref "C56") (pin "1") (pinfunction "1_1") (pintype "passive"))
      (node (ref "C57") (pin "1") (pinfunction "1_1") (pintype "passive"))
      (node (ref "C58") (pin "2") (pinfunction "2_2") (pintype "passive"))
      (node (ref "C59") (pin "2") (pinfunction "2_2") (pintype "passive"))
      (node (ref "C61") (pin "2") (pinfunction "2_2") (pintype "passive"))
      (node (ref "C63") (pin "2") (pinfunction "2_2") (pintype "passive"))
      (node (ref "C65") (pin "2") (pinfunction "2_2") (pintype "passive"))
      (node (ref "C66") (pin "2") (pinfunction "2_2") (pintype "passive"))
      (node (ref "C67") (pin "2") (pinfunction "2_2") (pintype "passive"))
      (node (ref "C69") (pin "2") (pinfunction "2_2") (pintype "passive"))
      (node (ref "C70") (pin "2") (pinfunction "2_2") (pintype "passive"))
      (node (ref "DA10") (pin "2") (pinfunction "GND_2") (pintype "power_in"))
      (node (ref "DA12") (pin "4") (pinfunction "GND_4") (pintype "power_in"))
      (node (ref "DA6") (pin "5") (pinfunction "GND_5") (pintype "passive"))
      (node (ref "DA7") (pin "3") (pinfunction "EMITTER_3") (pintype "passive"))
      (node (ref "DA8") (pin "3") (pinfunction "EMITTER_3") (pintype "passive"))
      (node (ref "DD8") (pin "7") (pinfunction "GND_7") (pintype "power_in"))
      (node (ref "R40") (pin "1") (pinfunction "1_1") (pintype "passive"))
      (node (ref "R51") (pin "1") (pinfunction "1_1") (pintype "passive"))
      (node (ref "R52") (pin "2") (pinfunction "2_2") (pintype "passive"))
      (node (ref "R56") (pin "1") (pinfunction "1_1") (pintype "passive"))
      (node (ref "R61") (pin "1") (pinfunction "1_1") (pintype "passive"))
      (node (ref "R64") (pin "1") (pinfunction "1_1") (pintype "passive"))
      (node (ref "R71") (pin "1") (pinfunction "1_1") (pintype "passive"))
      (node (ref "R73") (pin "1") (pinfunction "1_1") (pintype "passive"))
      (node (ref "SB17") (pin "1") (pinfunction "1_1") (pintype "passive"))
      (node (ref "SB17") (pin "2") (pinfunction "2_2") (pintype "passive"))
      (node (ref "VT4") (pin "2") (pinfunction "C_2") (pintype "passive"))
      (node (ref "VT7") (pin "3") (pinfunction "E_3") (pintype "passive"))
      (node (ref "VT8") (pin "3") (pinfunction "E_3") (pintype "passive"))
      (node (ref "XS4") (pin "1") (pinfunction "1_1") (pintype "passive"))
      (node (ref "XS4") (pin "2") (pinfunction "2_2") (pintype "passive"))
      (node (ref "XS5") (pin "2") (pinfunction "2_2") (pintype "passive"))
      (node (ref "XS6") (pin "2") (pinfunction "2_2") (pintype "passive"))
    )
    (net (code "10") (name "I2C_CH1_ALERT") (class "Default")
      (node (ref "DA5") (pin "7") (pinfunction "V01_7") (pintype "passive"))
      (node (ref "R47") (pin "2") (pinfunction "2_2") (pintype "passive"))
    )
    (net (code "11") (name "I2C_CH1_SCL") (class "Default")
      (node (ref "R38") (pin "1") (pinfunction "1_1") (pintype "passive"))
      (node (ref "VT2") (pin "1") (pinfunction "B_1") (pintype "passive"))
    )
    (net (code "12") (name "I2C_CH1_SDA") (class "Default")
      (node (ref "R36") (pin "1") (pinfunction "1_1") (pintype "passive"))
      (node (ref "VD5") (pin "2") (pinfunction "ANODE_2") (pintype "passive"))
      (node (ref "VT1") (pin "1") (pinfunction "B_1") (pintype "passive"))
    )
    (net (code "13") (name "Net-(A2-IN+)") (class "Default")
      (node (ref "A2") (pin "1") (pinfunction "IN+_1") (pintype "input"))
      (node (ref "C68") (pin "2") (pinfunction "2_2") (pintype "passive"))
      (node (ref "R74") (pin "2") (pinfunction "2_2") (pintype "passive"))
    )
    (net (code "14") (name "Net-(A2-IN-)") (class "Default")
      (node (ref "A2") (pin "2") (pinfunction "IN-_2") (pintype "input"))
      (node (ref "C68") (pin "1") (pinfunction "1_1") (pintype "passive"))
      (node (ref "R75") (pin "2") (pinfunction "2_2") (pintype "passive"))
    )
    (net (code "15") (name "Net-(C48-Pad1)") (class "Default")
      (node (ref "C48") (pin "1") (pinfunction "1_1") (pintype "passive"))
      (node (ref "R39") (pin "2") (pinfunction "2_2") (pintype "passive"))
      (node (ref "R42") (pin "1") (pinfunction "1_1") (pintype "passive"))
      (node (ref "R43") (pin "1") (pinfunction "1_1") (pintype "passive"))
      (node (ref "XS3") (pin "1") (pinfunction "1_1") (pintype "passive"))
      (node (ref "XS3") (pin "2") (pinfunction "2_2") (pintype "passive"))
    )
    (net (code "16") (name "Net-(C51-Pad1)") (class "Default")
      (node (ref "C51") (pin "1") (pinfunction "1_1") (pintype "passive"))
      (node (ref "R48") (pin "1") (pinfunction "1_1") (pintype "passive"))
      (node (ref "R53") (pin "1") (pinfunction "1_1") (pintype "passive"))
    )
    (net (code "17") (name "Net-(C63-Pad1)") (class "Default")
      (node (ref "C63") (pin "1") (pinfunction "1_1") (pintype "passive"))
      (node (ref "R65") (pin "1") (pinfunction "1_1") (pintype "passive"))
      (node (ref "R66") (pin "1") (pinfunction "1_1") (pintype "passive"))
    )
    (net (code "18") (name "Net-(DA5-ANODE1)") (class "Default")
      (node (ref "DA5") (pin "1") (pinfunction "ANODE1_1") (pintype "passive"))
      (node (ref "VT3") (pin "2") (pinfunction "C_2") (pintype "passive"))
    )
    (net (code "19") (name "Net-(DA5-ANODE2)") (class "Default")
      (node (ref "DA5") (pin "4") (pinfunction "ANODE2_4") (pintype "passive"))
      (node (ref "DA6") (pin "7") (pinfunction "V01_7") (pintype "passive"))
      (node (ref "R58") (pin "2") (pinfunction "2_2") (pintype "passive"))
      (node (ref "VD6") (pin "1") (pinfunction "CATHODE_1") (pintype "passive"))
    )
    (net (code "20") (name "Net-(DA5-CATHODE1)") (class "Default")
      (node (ref "DA5") (pin "2") (pinfunction "CATHODE1_2") (pintype "power_in"))
      (node (ref "R52") (pin "1") (pinfunction "1_1") (pintype "passive"))
    )
    (net (code "21") (name "Net-(DA5-CATHODE2)") (class "Default")
      (node (ref "DA5") (pin "3") (pinfunction "CATHODE2_3") (pintype "power_in"))
      (node (ref "VT4") (pin "3") (pinfunction "E_3") (pintype "passive"))
    )
    (net (code "22") (name "Net-(DA5-V02)") (class "Default")
      (node (ref "DA5") (pin "6") (pinfunction "V02_6") (pintype "passive"))
      (node (ref "DA6") (pin "1") (pinfunction "ANODE1_1") (pintype "passive"))
      (node (ref "R37") (pin "2") (pinfunction "2_2") (pintype "passive"))
      (node (ref "VD5") (pin "1") (pinfunction "CATHODE_1") (pintype "passive"))
    )
    (net (code "23") (name "Net-(DA6-ANODE2)") (class "Default")
      (node (ref "DA6") (pin "4") (pinfunction "ANODE2_4") (pintype "passive"))
      (node (ref "VT2") (pin "2") (pinfunction "C_2") (pintype "passive"))
    )
    (net (code "24") (name "Net-(DA6-CATHODE1)") (class "Default")
      (node (ref "DA6") (pin "2") (pinfunction "CATHODE1_2") (pintype "power_in"))
      (node (ref "VT1") (pin "3") (pinfunction "E_3") (pintype "passive"))
    )
    (net (code "25") (name "Net-(DA6-CATHODE2)") (class "Default")
      (node (ref "DA6") (pin "3") (pinfunction "CATHODE2_3") (pintype "power_in"))
      (node (ref "R41") (pin "2") (pinfunction "2_2") (pintype "passive"))
    )
    (net (code "26") (name "Net-(DA7-CATHODE)") (class "Default")
      (node (ref "DA7") (pin "2") (pinfunction "CATHODE_2") (pintype "power_in"))
      (node (ref "R44") (pin "2") (pinfunction "2_2") (pintype "passive"))
    )
    (net (code "27") (name "Net-(DA8-CATHODE)") (class "Default")
      (node (ref "DA8") (pin "2") (pinfunction "CATHODE_2") (pintype "power_in"))
      (node (ref "R45") (pin "2") (pinfunction "2_2") (pintype "passive"))
    )
    (net (code "28") (name "Net-(DA9-CATHODE)") (class "Default")
      (node (ref "DA9") (pin "2") (pinfunction "CATHODE_2") (pintype "power_in"))
      (node (ref "R46") (pin "2") (pinfunction "2_2") (pintype "passive"))
    )
    (net (code "29") (name "Net-(DA10-VIN)") (class "Default")
      (node (ref "C50") (pin "1") (pinfunction "1_1") (pintype "passive"))
      (node (ref "C52") (pin "1") (pinfunction "1_1") (pintype "passive"))
      (node (ref "DA10") (pin "3") (pinfunction "VIN_3") (pintype "power_in"))
      (node (ref "L3") (pin "2") (pinfunction "2_2") (pintype "passive"))
    )
    (net (code "30") (name "Net-(DA10-VOUT)") (class "Default")
      (node (ref "C58") (pin "1") (pinfunction "1_1") (pintype "passive"))
      (node (ref "C59") (pin "1") (pinfunction "1_1") (pintype "passive"))
      (node (ref "DA10") (pin "1") (pinfunction "VOUT_1") (pintype "power_in"))
      (node (ref "L6") (pin "1") (pinfunction "1_1") (pintype "passive"))
    )
    (net (code "31") (name "Net-(DA11A-1IN+)") (class "Default")
      (node (ref "C48") (pin "2") (pinfunction "2_2") (pintype "passive"))
      (node (ref "DA11") (pin "3") (pinfunction "1IN+_3") (pintype "input"))
      (node (ref "R39") (pin "1") (pinfunction "1_1") (pintype "passive"))
      (node (ref "R40") (pin "2") (pinfunction "2_2") (pintype "passive"))
    )
    (net (code "32") (name "Net-(DA11A-1IN-)") (class "Default")
      (node (ref "DA11") (pin "2") (pinfunction "1IN-_2") (pintype "input"))
      (node (ref "R48") (pin "2") (pinfunction "2_2") (pintype "passive"))
      (node (ref "R54") (pin "2") (pinfunction "2_2") (pintype "passive"))
    )
    (net (code "33") (name "Net-(DA11A-1OUT)") (class "Default")
      (node (ref "C60") (pin "1") (pinfunction "1_1") (pintype "passive"))
      (node (ref "DA11") (pin "1") (pinfunction "1OUT_1") (pintype "output"))
      (node (ref "R53") (pin "2") (pinfunction "2_2") (pintype "passive"))
    )
    (net (code "34") (name "Net-(DA11A-GND)") (class "Default")
      (node (ref "C55") (pin "1") (pinfunction "1_1") (pintype "passive"))
      (node (ref "C56") (pin "2") (pinfunction "2_2") (pintype "passive"))
      (node (ref "DA11") (pin "4") (pinfunction "GND_4") (pintype "power_in"))
      (node (ref "L5") (pin "1") (pinfunction "1_1") (pintype "passive"))
    )
    (net (code "35") (name "Net-(DA11A-VCC)") (class "Default")
      (node (ref "C53") (pin "1") (pinfunction "1_1") (pintype "passive"))
      (node (ref "C54") (pin "1") (pinfunction "1_1") (pintype "passive"))
      (node (ref "DA11") (pin "8") (pinfunction "VCC_8") (pintype "power_in"))
      (node (ref "L4") (pin "1") (pinfunction "1_1") (pintype "passive"))
    )
    (net (code "36") (name "Net-(DA11B-2IN+)") (class "Default")
      (node (ref "C62") (pin "2") (pinfunction "2_2") (pintype "passive"))
      (node (ref "DA11") (pin "5") (pinfunction "2IN+_5") (pintype "input"))
      (node (ref "R63") (pin "1") (pinfunction "1_1") (pintype "passive"))
      (node (ref "R64") (pin "2") (pinfunction "2_2") (pintype "passive"))
    )
    (net (code "37") (name "Net-(DA11B-2IN-)") (class "Default")
      (node (ref "DA11") (pin "6") (pinfunction "2IN-_6") (pintype "input"))
      (node (ref "R65") (pin "2") (pinfunction "2_2") (pintype "passive"))
      (node (ref "R67") (pin "2") (pinfunction "2_2") (pintype "passive"))
    )
    (net (code "38") (name "Net-(DA11B-2OUT)") (class "Default")
      (node (ref "C64") (pin "1") (pinfunction "1_1") (pintype "passive"))
      (node (ref "DA11") (pin "7") (pinfunction "2OUT_7") (pintype "output"))
      (node (ref "R66") (pin "2") (pinfunction "2_2") (pintype "passive"))
    )
    (net (code "39") (name "Net-(DA12A-1IN+)") (class "Default")
      (node (ref "C61") (pin "1") (pinfunction "1_1") (pintype "passive"))
      (node (ref "C62") (pin "1") (pinfunction "1_1") (pintype "passive"))
      (node (ref "DA12") (pin "3") (pinfunction "1IN+_3") (pintype "input"))
      (node (ref "R42") (pin "2") (pinfunction "2_2") (pintype "passive"))
      (node (ref "R43") (pin "2") (pinfunction "2_2") (pintype "passive"))
      (node (ref "R60") (pin "2") (pinfunction "2_2") (pintype "passive"))
      (node (ref "R63") (pin "2") (pinfunction "2_2") (pintype "passive"))
      (node (ref "R68") (pin "1") (pinfunction "1_1") (pintype "passive"))
      (node (ref "R69") (pin "1") (pinfunction "1_1") (pintype "passive"))
    )
    (net (code "40") (name "Net-(DA12A-1IN-)") (class "Default")
      (node (ref "DA12") (pin "1") (pinfunction "1OUT_1") (pintype "output"))
      (node (ref "DA12") (pin "2") (pinfunction "1IN-_2") (pintype "input"))
      (node (ref "R74") (pin "1") (pinfunction "1_1") (pintype "passive"))
    )
    (net (code "41") (name "Net-(DA12A-VCC)") (class "Default")
      (node (ref "C66") (pin "1") (pinfunction "1_1") (pintype "passive"))
      (node (ref "C67") (pin "1") (pinfunction "1_1") (pintype "passive"))
      (node (ref "DA12") (pin "8") (pinfunction "VCC_8") (pintype "power_in"))
      (node (ref "L7") (pin "1") (pinfunction "1_1") (pintype "passive"))
    )
    (net (code "42") (name "Net-(DA12B-2IN+)") (class "Default")
      (node (ref "C65") (pin "1") (pinfunction "1_1") (pintype "passive"))
      (node (ref "DA12") (pin "5") (pinfunction "2IN+_5") (pintype "input"))
      (node (ref "K1") (pin "1") (pinfunction "1_1") (pintype "passive"))
      (node (ref "R68") (pin "2") (pinfunction "2_2") (pintype "passive"))
      (node (ref "R69") (pin "2") (pinfunction "2_2") (pintype "passive"))
      (node (ref "R72") (pin "2") (pinfunction "2_2") (pintype "passive"))
    )
    (net (code "43") (name "Net-(DA12B-2IN-)") (class "Default")
      (node (ref "DA12") (pin "6") (pinfunction "2IN-_6") (pintype "input"))
      (node (ref "DA12") (pin "7") (pinfunction "2OUT_7") (pintype "output"))
      (node (ref "R75") (pin "1") (pinfunction "1_1") (pintype "passive"))
    )
    (net (code "44") (name "Net-(DD8A-B0)") (class "Default")
      (node (ref "DD8") (pin "2") (pinfunction "B0_2") (pintype "input"))
      (node (ref "DD8") (pin "4") (pinfunction "Y1_4") (pintype "output"))
    )
    (net (code "45") (name "Net-(DD8A-Y0)") (class "Default")
      (node (ref "DD8") (pin "3") (pinfunction "Y0_3") (pintype "output"))
      (node (ref "DD8") (pin "5") (pinfunction "A1_5") (pintype "input"))
      (node (ref "DD8") (pin "8") (pinfunction "A2_8") (pintype "input"))
      (node (ref "DD8") (pin "9") (pinfunction "B2_9") (pintype "input"))
    )
    (net (code "46") (name "Net-(DD8C-Y2)") (class "Default")
      (node (ref "DD8") (pin "10") (pinfunction "Y2_10") (pintype "output"))
      (node (ref "DD8") (pin "13") (pinfunction "B3_13") (pintype "input"))
    )
    (net (code "47") (name "Net-(DD8D-Y3)") (class "Default")
      (node (ref "DD8") (pin "11") (pinfunction "Y3_11") (pintype "output"))
      (node (ref "R77") (pin "1") (pinfunction "1_1") (pintype "passive"))
    )
    (net (code "48") (name "Net-(VD7-A)") (class "Default")
      (node (ref "K1") (pin "2") (pinfunction "2_2") (pintype "passive"))
      (node (ref "VD7") (pin "2") (pinfunction "A_2") (pintype "passive"))
      (node (ref "VT8") (pin "2") (pinfunction "C_2") (pintype "passive"))
    )
    (net (code "49") (name "Net-(VT5-B)") (class "Default")
      (node (ref "C60") (pin "2") (pinfunction "2_2") (pintype "passive"))
      (node (ref "R55") (pin "1") (pinfunction "1_1") (pintype "passive"))
      (node (ref "R56") (pin "2") (pinfunction "2_2") (pintype "passive"))
      (node (ref "VT5") (pin "3") (pinfunction "B_3") (pintype "passive"))
    )
    (net (code "50") (name "Net-(VT5-C)") (class "Default")
      (node (ref "R55") (pin "2") (pinfunction "2_2") (pintype "passive"))
      (node (ref "R60") (pin "1") (pinfunction "1_1") (pintype "passive"))
      (node (ref "VT5") (pin "2") (pinfunction "C_2") (pintype "passive"))
    )
    (net (code "51") (name "Net-(VT5-E)") (class "Default")
      (node (ref "R54") (pin "1") (pinfunction "1_1") (pintype "passive"))
      (node (ref "R61") (pin "2") (pinfunction "2_2") (pintype "passive"))
      (node (ref "VT5") (pin "1") (pinfunction "E_1") (pintype "passive"))
    )
    (net (code "52") (name "Net-(VT6-B)") (class "Default")
      (node (ref "C64") (pin "2") (pinfunction "2_2") (pintype "passive"))
      (node (ref "R70") (pin "1") (pinfunction "1_1") (pintype "passive"))
      (node (ref "R71") (pin "2") (pinfunction "2_2") (pintype "passive"))
      (node (ref "VT6") (pin "3") (pinfunction "B_3") (pintype "passive"))
    )
    (net (code "53") (name "Net-(VT6-C)") (class "Default")
      (node (ref "R70") (pin "2") (pinfunction "2_2") (pintype "passive"))
      (node (ref "R72") (pin "1") (pinfunction "1_1") (pintype "passive"))
      (node (ref "VT6") (pin "2") (pinfunction "C_2") (pintype "passive"))
    )
    (net (code "54") (name "Net-(VT6-E)") (class "Default")
      (node (ref "R67") (pin "1") (pinfunction "1_1") (pintype "passive"))
      (node (ref "R73") (pin "2") (pinfunction "2_2") (pintype "passive"))
      (node (ref "VT6") (pin "1") (pinfunction "E_1") (pintype "passive"))
    )
    (net (code "55") (name "VCC_3V3P") (class "Default")
      (node (ref "C49") (pin "2") (pinfunction "2_2") (pintype "passive"))
      (node (ref "DA5") (pin "8") (pinfunction "VCC_8") (pintype "power_in"))
      (node (ref "R36") (pin "2") (pinfunction "2_2") (pintype "passive"))
      (node (ref "R37") (pin "1") (pinfunction "1_1") (pintype "passive"))
      (node (ref "R38") (pin "2") (pinfunction "2_2") (pintype "passive"))
      (node (ref "R47") (pin "1") (pinfunction "1_1") (pintype "passive"))
      (node (ref "VT2") (pin "3") (pinfunction "E_3") (pintype "passive"))
    )
    (net (code "56") (name "VCC_10V0N") (class "Default")
      (node (ref "C47") (pin "2") (pinfunction "2_2") (pintype "passive"))
      (node (ref "L5") (pin "2") (pinfunction "2_2") (pintype "passive"))
      (node (ref "XS5") (pin "3") (pinfunction "3_3") (pintype "passive"))
    )
    (net (code "57") (name "VCC_10V0P") (class "Default")
      (node (ref "C46") (pin "1") (pinfunction "1_1") (pintype "passive"))
      (node (ref "L4") (pin "2") (pinfunction "2_2") (pintype "passive"))
      (node (ref "L7") (pin "2") (pinfunction "2_2") (pintype "passive"))
      (node (ref "XS5") (pin "1") (pinfunction "1_1") (pintype "passive"))
    )
    (net (code "58") (name "VCC_PWR_5V0P") (class "Default")
      (node (ref "A2") (pin "8") (pinfunction "VCC_8") (pintype "power_in"))
      (node (ref "C57") (pin "2") (pinfunction "2_2") (pintype "passive"))
      (node (ref "C69") (pin "1") (pinfunction "1_1") (pintype "passive"))
      (node (ref "C70") (pin "1") (pinfunction "1_1") (pintype "passive"))
      (node (ref "DA6") (pin "8") (pinfunction "VCC_8") (pintype "power_in"))
      (node (ref "DA9") (pin "4") (pinfunction "COLLECTOR_4") (pintype "passive"))
      (node (ref "DD8") (pin "14") (pinfunction "VCC_14") (pintype "power_in"))
      (node (ref "L6") (pin "2") (pinfunction "2_2") (pintype "passive"))
      (node (ref "R49") (pin "2") (pinfunction "2_2") (pintype "passive"))
      (node (ref "R50") (pin "2") (pinfunction "2_2") (pintype "passive"))
      (node (ref "R57") (pin "2") (pinfunction "2_2") (pintype "passive"))
      (node (ref "R58") (pin "1") (pinfunction "1_1") (pintype "passive"))
      (node (ref "R59") (pin "1") (pinfunction "1_1") (pintype "passive"))
      (node (ref "R62") (pin "1") (pinfunction "1_1") (pintype "passive"))
      (node (ref "R76") (pin "2") (pinfunction "2_2") (pintype "passive"))
      (node (ref "VT3") (pin "3") (pinfunction "E_3") (pintype "passive"))
    )
    (net (code "59") (name "VCC_PWR_12V0P") (class "Default")
      (node (ref "K1") (pin "4") (pinfunction "4_4") (pintype "passive"))
      (node (ref "L3") (pin "1") (pinfunction "1_1") (pintype "passive"))
      (node (ref "VD7") (pin "1") (pinfunction "C_1") (pintype "passive"))
      (node (ref "XS6") (pin "1") (pinfunction "1_1") (pintype "passive"))
    )
    (net (code "60") (name "unconnected-(A2-VBS-Pad3)") (class "Default")
      (node (ref "A2") (pin "3") (pinfunction "VBS_3") (pintype "passive"))
    )
    (net (code "61") (name "unconnected-(K1-Pad5)") (class "Default")
      (node (ref "K1") (pin "5") (pinfunction "5_5") (pintype "passive"))
    )
    (net (code "62") (name "unconnected-(K1-Pad6)") (class "Default")
      (node (ref "K1") (pin "6") (pinfunction "6_6") (pintype "passive+no_connect"))
    )
    (net (code "63") (name "unconnected-(R77-Pad2)") (class "Default")
      (node (ref "R77") (pin "2") (pinfunction "2_2") (pintype "passive"))
    )
    (net (code "64") (name "unconnected-(VT7-B-Pad1)") (class "Default")
      (node (ref "VT7") (pin "1") (pinfunction "B_1") (pintype "passive"))
    )
    (net (code "65") (name "unconnected-(VT7-C-Pad2)") (class "Default")
      (node (ref "VT7") (pin "2") (pinfunction "C_2") (pintype "passive"))
    )
    (net (code "66") (name "unconnected-(VT8-B-Pad1)") (class "Default")
      (node (ref "VT8") (pin "1") (pinfunction "B_1") (pintype "passive"))
    )
  )
)
